# IBVG-DRIVER.net
KiCad netlist of a schematic drawn in Altium Designer
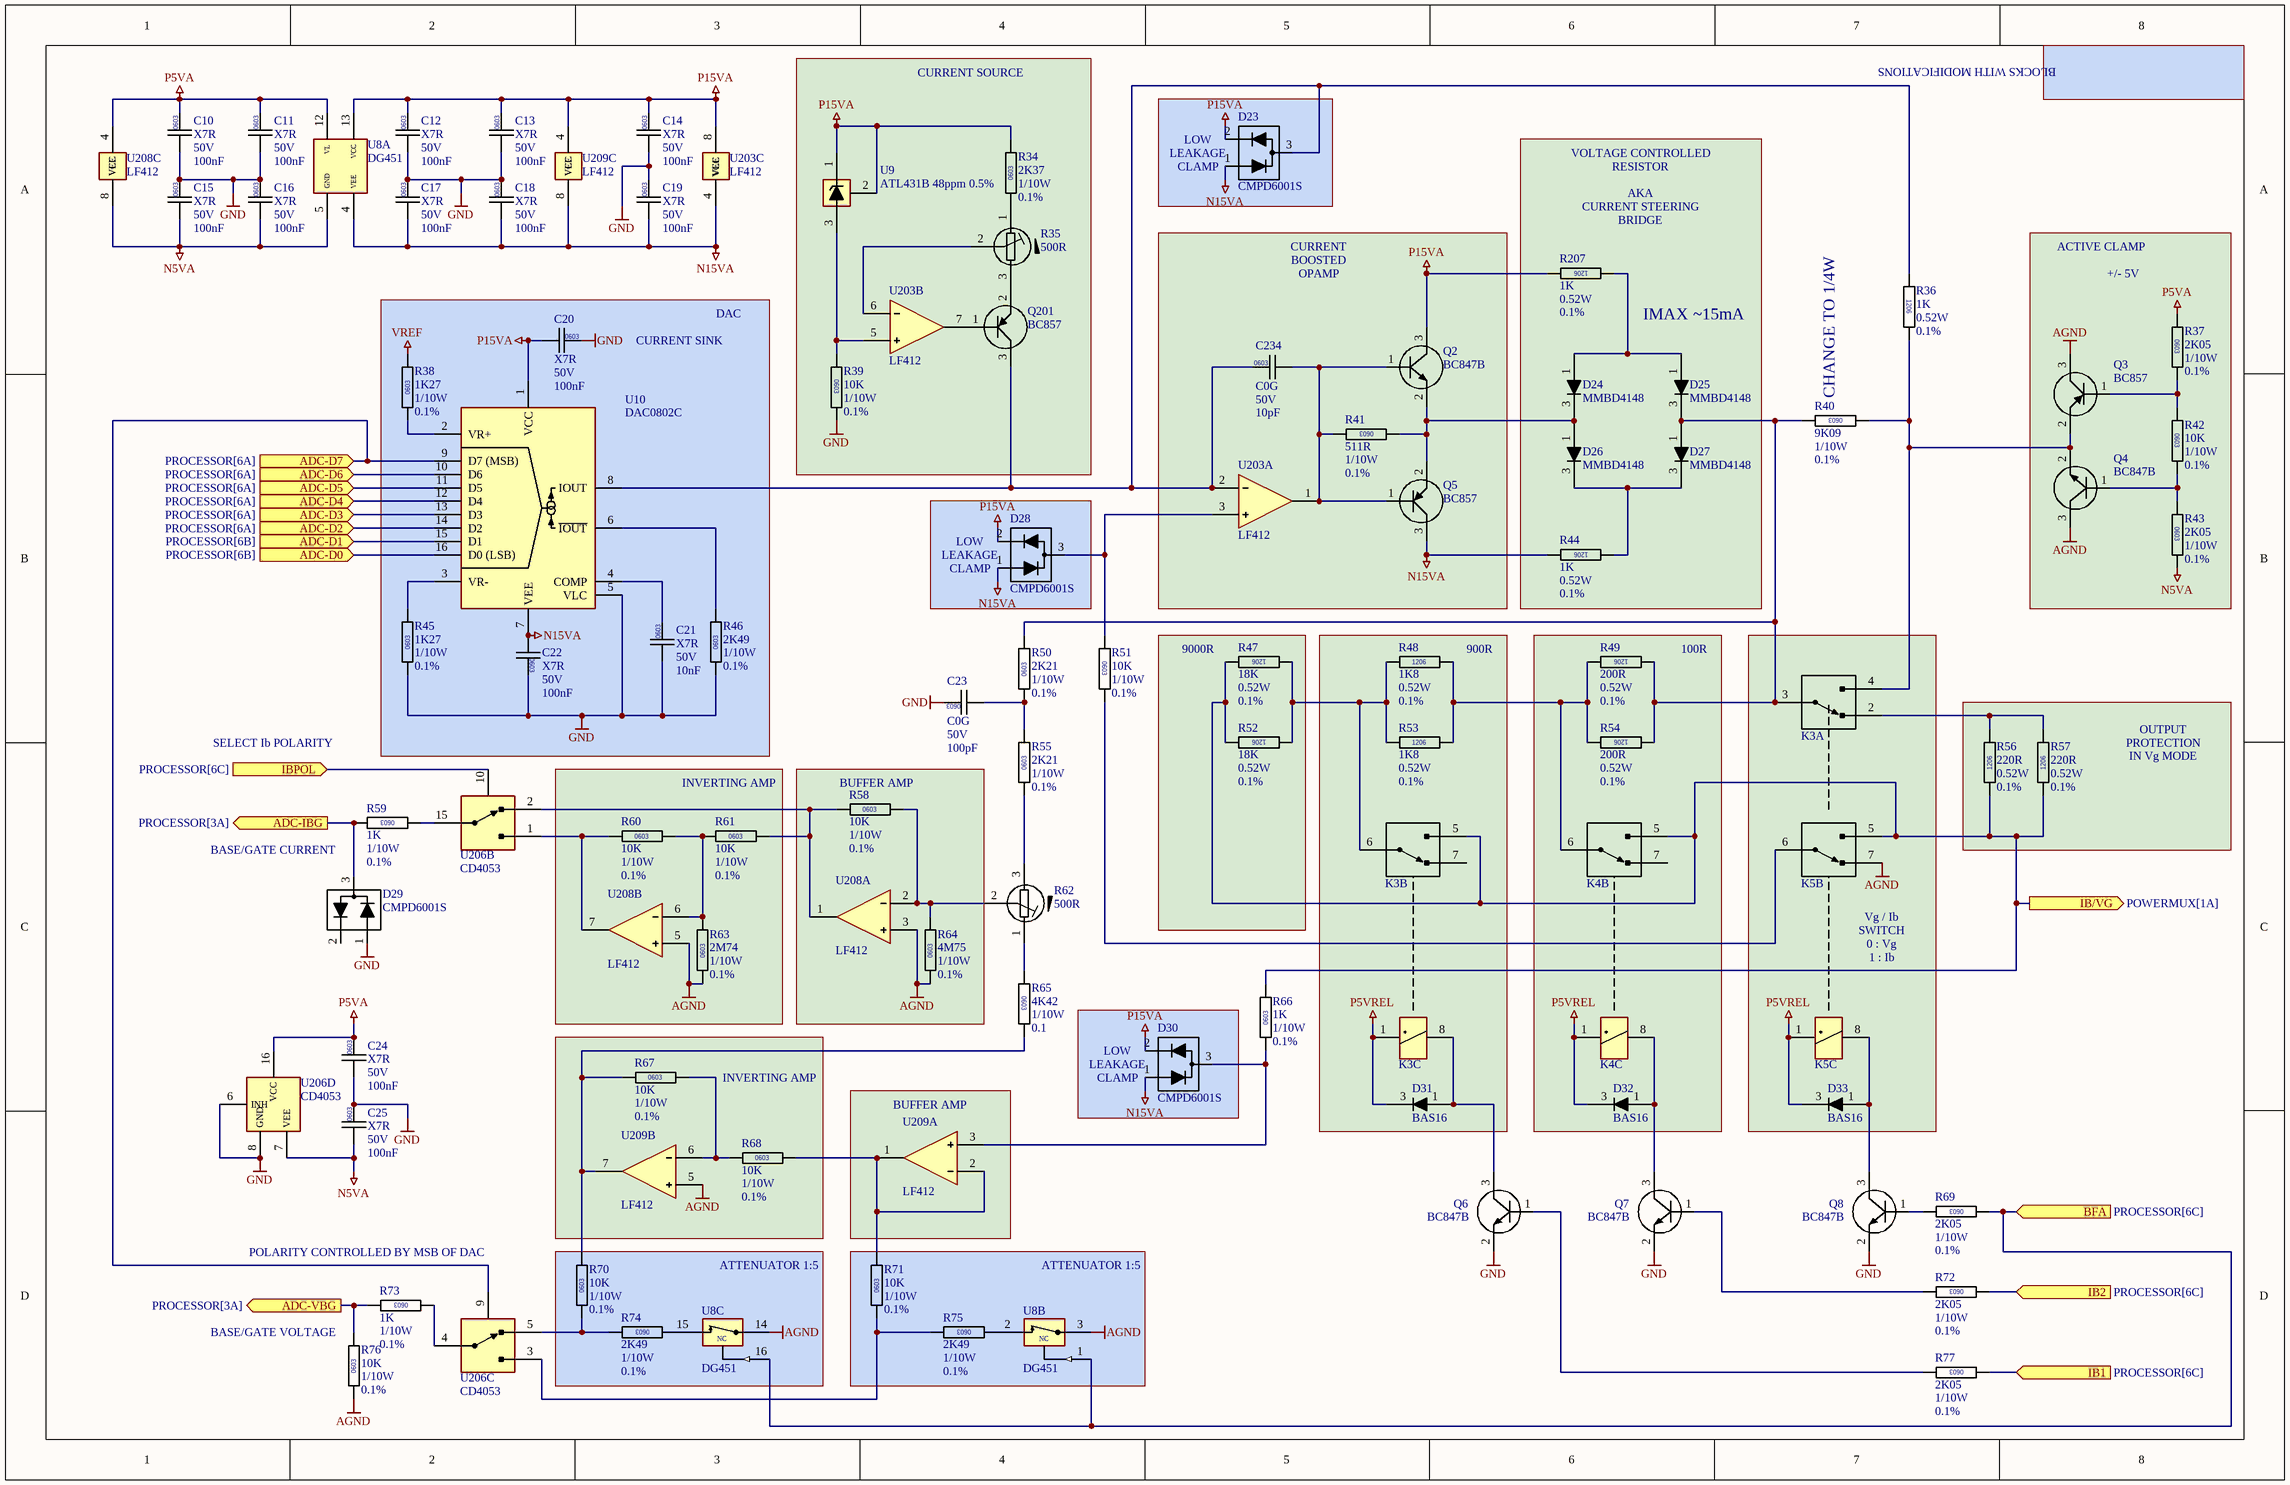
[diagram p0: IBVG-DRIVER.SchDoc]

(export (version "E")
  (design (tool "Eeschema 10.0.6"))
  (components
    (comp (ref "C10")
      (value "CAP0603")
      (footprint "CAPC0603")
      (description "CAPACITOR,CERAMIC,100nF,50V,X7R,0603")
      (fields
        (field (name "DIELECTRIC") "X7R")
        (field (name "VOLTAGE") "50V")
        (field (name "CAPACITANCE") "100nF")
      )
      (libsource (lib "CAPACITORS") (part "CAPC-0603-100nF-50V-X7R"))
    )
    (comp (ref "C11")
      (value "CAP0603")
      (footprint "CAPC0603")
      (description "CAPACITOR,CERAMIC,100nF,50V,X7R,0603")
      (fields
        (field (name "DIELECTRIC") "X7R")
        (field (name "VOLTAGE") "50V")
        (field (name "CAPACITANCE") "100nF")
      )
      (libsource (lib "CAPACITORS") (part "CAPC-0603-100nF-50V-X7R"))
    )
    (comp (ref "C12")
      (value "CAP0603")
      (footprint "CAPC0603")
      (description "CAPACITOR,CERAMIC,100nF,50V,X7R,0603")
      (fields
        (field (name "DIELECTRIC") "X7R")
        (field (name "VOLTAGE") "50V")
        (field (name "CAPACITANCE") "100nF")
      )
      (libsource (lib "CAPACITORS") (part "CAPC-0603-100nF-50V-X7R"))
    )
    (comp (ref "C13")
      (value "CAP0603")
      (footprint "CAPC0603")
      (description "CAPACITOR,CERAMIC,100nF,50V,X7R,0603")
      (fields
        (field (name "DIELECTRIC") "X7R")
        (field (name "VOLTAGE") "50V")
        (field (name "CAPACITANCE") "100nF")
      )
      (libsource (lib "CAPACITORS") (part "CAPC-0603-100nF-50V-X7R"))
    )
    (comp (ref "C14")
      (value "CAP0603")
      (footprint "CAPC0603")
      (description "CAPACITOR,CERAMIC,100nF,50V,X7R,0603")
      (fields
        (field (name "DIELECTRIC") "X7R")
        (field (name "VOLTAGE") "50V")
        (field (name "CAPACITANCE") "100nF")
      )
      (libsource (lib "CAPACITORS") (part "CAPC-0603-100nF-50V-X7R"))
    )
    (comp (ref "C15")
      (value "CAP0603")
      (footprint "CAPC0603")
      (description "CAPACITOR,CERAMIC,100nF,50V,X7R,0603")
      (fields
        (field (name "DIELECTRIC") "X7R")
        (field (name "VOLTAGE") "50V")
        (field (name "CAPACITANCE") "100nF")
      )
      (libsource (lib "CAPACITORS") (part "CAPC-0603-100nF-50V-X7R"))
    )
    (comp (ref "C16")
      (value "CAP0603")
      (footprint "CAPC0603")
      (description "CAPACITOR,CERAMIC,100nF,50V,X7R,0603")
      (fields
        (field (name "DIELECTRIC") "X7R")
        (field (name "VOLTAGE") "50V")
        (field (name "CAPACITANCE") "100nF")
      )
      (libsource (lib "CAPACITORS") (part "CAPC-0603-100nF-50V-X7R"))
    )
    (comp (ref "C17")
      (value "CAP0603")
      (footprint "CAPC0603")
      (description "CAPACITOR,CERAMIC,100nF,50V,X7R,0603")
      (fields
        (field (name "DIELECTRIC") "X7R")
        (field (name "VOLTAGE") "50V")
        (field (name "CAPACITANCE") "100nF")
      )
      (libsource (lib "CAPACITORS") (part "CAPC-0603-100nF-50V-X7R"))
    )
    (comp (ref "C18")
      (value "CAP0603")
      (footprint "CAPC0603")
      (description "CAPACITOR,CERAMIC,100nF,50V,X7R,0603")
      (fields
        (field (name "DIELECTRIC") "X7R")
        (field (name "VOLTAGE") "50V")
        (field (name "CAPACITANCE") "100nF")
      )
      (libsource (lib "CAPACITORS") (part "CAPC-0603-100nF-50V-X7R"))
    )
    (comp (ref "C19")
      (value "CAP0603")
      (footprint "CAPC0603")
      (description "CAPACITOR,CERAMIC,100nF,50V,X7R,0603")
      (fields
        (field (name "DIELECTRIC") "X7R")
        (field (name "VOLTAGE") "50V")
        (field (name "CAPACITANCE") "100nF")
      )
      (libsource (lib "CAPACITORS") (part "CAPC-0603-100nF-50V-X7R"))
    )
    (comp (ref "C20")
      (value "CAP0603")
      (footprint "CAPC0603")
      (description "CAPACITOR,CERAMIC,100nF,50V,X7R,0603")
      (fields
        (field (name "DIELECTRIC") "X7R")
        (field (name "VOLTAGE") "50V")
        (field (name "CAPACITANCE") "100nF")
      )
      (libsource (lib "CAPACITORS") (part "CAPC-0603-100nF-50V-X7R"))
    )
    (comp (ref "C21")
      (value "CAP0603")
      (footprint "CAPC0603")
      (description "CAPACITOR,CERAMIC,10nF,50V,X7R,0603")
      (fields
        (field (name "DIELECTRIC") "X7R")
        (field (name "VOLTAGE") "50V")
        (field (name "CAPACITANCE") "10nF")
      )
      (libsource (lib "CAPACITORS") (part "CAPC-0603-10nF-50V-X7R"))
    )
    (comp (ref "C22")
      (value "CAP0603")
      (footprint "CAPC0603")
      (description "CAPACITOR,CERAMIC,100nF,50V,X7R,0603")
      (fields
        (field (name "DIELECTRIC") "X7R")
        (field (name "VOLTAGE") "50V")
        (field (name "CAPACITANCE") "100nF")
      )
      (libsource (lib "CAPACITORS") (part "CAPC-0603-100nF-50V-X7R"))
    )
    (comp (ref "C23")
      (value "CAP0603")
      (footprint "CAPC0603")
      (description "CAPACITOR,CERAMIC,100pF,50V,C0G,0603")
      (fields
        (field (name "DIELECTRIC") "C0G")
        (field (name "VOLTAGE") "50V")
        (field (name "CAPACITANCE") "100pF")
      )
      (libsource (lib "CAPACITORS") (part "CAPC-0603-100pF-50V-C0G"))
    )
    (comp (ref "C24")
      (value "CAP0603")
      (footprint "CAPC0603")
      (description "CAPACITOR,CERAMIC,100nF,50V,X7R,0603")
      (fields
        (field (name "DIELECTRIC") "X7R")
        (field (name "VOLTAGE") "50V")
        (field (name "CAPACITANCE") "100nF")
      )
      (libsource (lib "CAPACITORS") (part "CAPC-0603-100nF-50V-X7R"))
    )
    (comp (ref "C25")
      (value "CAP0603")
      (footprint "CAPC0603")
      (description "CAPACITOR,CERAMIC,100nF,50V,X7R,0603")
      (fields
        (field (name "DIELECTRIC") "X7R")
        (field (name "VOLTAGE") "50V")
        (field (name "CAPACITANCE") "100nF")
      )
      (libsource (lib "CAPACITORS") (part "CAPC-0603-100nF-50V-X7R"))
    )
    (comp (ref "C234")
      (value "CAP0603")
      (footprint "CAPC0603")
      (description "CAPACITOR,CERAMIC,10pF,50V,C0G,0603")
      (fields
        (field (name "DIELECTRIC") "C0G")
        (field (name "VOLTAGE") "50V")
        (field (name "CAPACITANCE") "10pF")
      )
      (libsource (lib "CAPACITORS") (part "CAPC-0603-10PF-50V-C0G"))
    )
    (comp (ref "D23")
      (value "CMPD6001S")
      (footprint "SOT23")
      (description "DIODE,75V,250mA,SOT23,500pA ULTRA LOW LEAKAGE")
      (libsource (lib "DIODES") (part "DIODE-CENTRALSEMI-CMPD6001S"))
    )
    (comp (ref "D24")
      (value "MMBD4148")
      (description "DIODE,RECTIFIER,75V,0.3A,MMBD4148,SOT23")
      (libsource (lib "DIODES") (part "DIODE-RECTIFIER-DIODES-MMBD4148-SOT23"))
    )
    (comp (ref "D25")
      (value "MMBD4148")
      (description "DIODE,RECTIFIER,75V,0.3A,MMBD4148,SOT23")
      (libsource (lib "DIODES") (part "DIODE-RECTIFIER-DIODES-MMBD4148-SOT23"))
    )
    (comp (ref "D26")
      (value "MMBD4148")
      (description "DIODE,RECTIFIER,75V,0.3A,MMBD4148,SOT23")
      (libsource (lib "DIODES") (part "DIODE-RECTIFIER-DIODES-MMBD4148-SOT23"))
    )
    (comp (ref "D27")
      (value "MMBD4148")
      (description "DIODE,RECTIFIER,75V,0.3A,MMBD4148,SOT23")
      (libsource (lib "DIODES") (part "DIODE-RECTIFIER-DIODES-MMBD4148-SOT23"))
    )
    (comp (ref "D28")
      (value "CMPD6001S")
      (footprint "SOT23")
      (description "DIODE,75V,250mA,SOT23,500pA ULTRA LOW LEAKAGE")
      (libsource (lib "DIODES") (part "DIODE-CENTRALSEMI-CMPD6001S"))
    )
    (comp (ref "D29")
      (value "CMPD6001S")
      (footprint "SOT23")
      (description "DIODE,75V,250mA,SOT23,500pA ULTRA LOW LEAKAGE")
      (libsource (lib "DIODES") (part "DIODE-CENTRALSEMI-CMPD6001S"))
    )
    (comp (ref "D30")
      (value "CMPD6001S")
      (footprint "SOT23")
      (description "DIODE,75V,250mA,SOT23,500pA ULTRA LOW LEAKAGE")
      (libsource (lib "DIODES") (part "DIODE-CENTRALSEMI-CMPD6001S"))
    )
    (comp (ref "D31")
      (value "BAS16")
      (footprint "SOT23")
      (description "DIODE,RECTIFIER,75V,0.3A,BAS16,SOT23")
      (libsource (lib "DIODES") (part "DIODE-RECTIFIER-DIODES-BAS16-SOT23"))
    )
    (comp (ref "D32")
      (value "BAS16")
      (footprint "SOT23")
      (description "DIODE,RECTIFIER,75V,0.3A,BAS16,SOT23")
      (libsource (lib "DIODES") (part "DIODE-RECTIFIER-DIODES-BAS16-SOT23"))
    )
    (comp (ref "D33")
      (value "BAS16")
      (footprint "SOT23")
      (description "DIODE,RECTIFIER,75V,0.3A,BAS16,SOT23")
      (libsource (lib "DIODES") (part "DIODE-RECTIFIER-DIODES-BAS16-SOT23"))
    )
    (comp (ref "K3")
      (value "RELAY-KEMET-UA2-5NJ")
      (footprint "RELAY-KEMET-UA2-5NJ")
      (description "RELAY,DPDT,1A,250VAC,220VDC,5V COIL,KEMET,UA2-5NJ")
      (libsource (lib "RELAYS") (part "RELAY-KEMET-UA2-5NJ"))
    )
    (comp (ref "K4")
      (value "RELAY-KEMET-UA2-5NJ")
      (footprint "RELAY-KEMET-UA2-5NJ")
      (description "RELAY,DPDT,1A,250VAC,220VDC,5V COIL,KEMET,UA2-5NJ")
      (libsource (lib "RELAYS") (part "RELAY-KEMET-UA2-5NJ"))
    )
    (comp (ref "K5")
      (value "RELAY-KEMET-UA2-5NJ")
      (footprint "RELAY-KEMET-UA2-5NJ")
      (description "RELAY,DPDT,1A,250VAC,220VDC,5V COIL,KEMET,UA2-5NJ")
      (libsource (lib "") (part "RELAY-KEMET-UA2-5NJ_1"))
    )
    (comp (ref "Q2")
      (value "BC847B")
      (footprint "SOT23")
      (description "XSTR,NPN,45V,0.1A,,BC847B,SOT23")
      (libsource (lib "TRANSISTORS") (part "XSTR-NPN-BC847"))
    )
    (comp (ref "Q3")
      (value "BC857")
      (footprint "SOT23")
      (description "XSTR,PNP,SOT23,BC857,SOT23")
      (libsource (lib "TRANSISTORS") (part "XSTR-PNP-BC857"))
    )
    (comp (ref "Q4")
      (value "BC847B")
      (footprint "SOT23")
      (description "XSTR,NPN,45V,0.1A,,BC847B,SOT23")
      (libsource (lib "TRANSISTORS") (part "XSTR-NPN-BC847"))
    )
    (comp (ref "Q5")
      (value "BC857")
      (footprint "SOT23")
      (description "XSTR,PNP,SOT23,BC857,SOT23")
      (libsource (lib "TRANSISTORS") (part "XSTR-PNP-BC857"))
    )
    (comp (ref "Q6")
      (value "BC847B")
      (footprint "SOT23")
      (description "XSTR,NPN,45V,0.1A,,BC847B,SOT23")
      (libsource (lib "TRANSISTORS") (part "XSTR-NPN-BC847"))
    )
    (comp (ref "Q7")
      (value "BC847B")
      (footprint "SOT23")
      (description "XSTR,NPN,45V,0.1A,,BC847B,SOT23")
      (libsource (lib "TRANSISTORS") (part "XSTR-NPN-BC847"))
    )
    (comp (ref "Q8")
      (value "BC847B")
      (footprint "SOT23")
      (description "XSTR,NPN,45V,0.1A,,BC847B,SOT23")
      (libsource (lib "TRANSISTORS") (part "XSTR-NPN-BC847"))
    )
    (comp (ref "Q201")
      (value "BC857")
      (footprint "SOT23")
      (description "XSTR,PNP,SOT23,BC857,SOT23")
      (libsource (lib "TRANSISTORS") (part "XSTR-PNP-BC857"))
    )
    (comp (ref "R34")
      (value "2K37")
      (footprint "RESC0603")
      (description "RESISTOR,2K37,0.1%,100mW,0603 (1608)")
      (fields
        (field (name "POWER") "1/10W")
        (field (name "TOLERANCE") "0.1%")
        (field (name "Comment") "RESC0603")
      )
      (libsource (lib "RESISTORS") (part "RESC-0603-2K37-0.1%-1/10W"))
    )
    (comp (ref "R35")
      (value "500R")
      (footprint "TRIMMER-BOURNS-3214X")
      (description "RESISTOR,MULTITURN,VERTICAL,5T,500R")
      (fields (field (name "Comment") "TRIMMER-BOURNS-3214X-1-501"))
      (libsource (lib "RESISTORS") (part "TRIMMER-BOURNS-3214X-1-501"))
    )
    (comp (ref "R36")
      (value "1K")
      (footprint "RESC1206")
      (description "RESISTOR,1K,1206,0.1%,520mW,1206")
      (fields
        (field (name "POWER") "0.52W")
        (field (name "TOLERANCE") "0.1%")
        (field (name "Comment") "RESC1206")
      )
      (libsource (lib "RESISTORS") (part "RESC-1206-1K-0.1%-1/2W"))
    )
    (comp (ref "R37")
      (value "2K05")
      (footprint "RESC0603")
      (description "RESISTOR,2K05,0.11%,100mW,0603 (1608)")
      (fields
        (field (name "POWER") "1/10W")
        (field (name "TOLERANCE") "0.1%")
        (field (name "Comment") "RESC0603")
      )
      (libsource (lib "RESISTORS") (part "RESC-0603-2K05-0.1%-1/10W"))
    )
    (comp (ref "R38")
      (value "1K27")
      (footprint "RESC0603")
      (description "RESISTOR,1K27,0.1%,100mW,0603 (1608)")
      (fields
        (field (name "POWER") "1/10W")
        (field (name "TOLERANCE") "0.1%")
        (field (name "Comment") "RESC0603")
      )
      (libsource (lib "RESISTORS") (part "RESC-0603-1K27-0.1%-1/10W"))
    )
    (comp (ref "R39")
      (value "10K")
      (footprint "RESC0603")
      (description "RESISTOR,10K,0.1%,100mW,0603 (1608)")
      (fields
        (field (name "POWER") "1/10W")
        (field (name "TOLERANCE") "0.1%")
        (field (name "Comment") "RESC0603")
      )
      (libsource (lib "RESISTORS") (part "RESC-0603-10K-0.1%-1/10W"))
    )
    (comp (ref "R40")
      (value "9K09")
      (footprint "RESC0603")
      (description "RESISTOR,9K09,0.1%,100mW,0603 (1608)")
      (fields
        (field (name "POWER") "1/10W")
        (field (name "TOLERANCE") "0.1%")
        (field (name "Comment") "RESC0603")
      )
      (libsource (lib "RESISTORS") (part "RESC-0603-9K09-0.1%-1/10W"))
    )
    (comp (ref "R41")
      (value "511R")
      (footprint "RESC0603")
      (description "RESISTOR,511R,0.1%,100mW,0603 (1608)")
      (fields
        (field (name "POWER") "1/10W")
        (field (name "TOLERANCE") "0.1%")
        (field (name "Comment") "RESC0603")
      )
      (libsource (lib "RESISTORS") (part "RESC-0603-511R-0.1%-1/10W"))
    )
    (comp (ref "R42")
      (value "10K")
      (footprint "RESC0603")
      (description "RESISTOR,10K,0.1%,100mW,0603 (1608)")
      (fields
        (field (name "POWER") "1/10W")
        (field (name "TOLERANCE") "0.1%")
        (field (name "Comment") "RESC0603")
      )
      (libsource (lib "RESISTORS") (part "RESC-0603-10K-0.1%-1/10W"))
    )
    (comp (ref "R43")
      (value "2K05")
      (footprint "RESC0603")
      (description "RESISTOR,2K05,0.11%,100mW,0603 (1608)")
      (fields
        (field (name "POWER") "1/10W")
        (field (name "TOLERANCE") "0.1%")
        (field (name "Comment") "RESC0603")
      )
      (libsource (lib "RESISTORS") (part "RESC-0603-2K05-0.1%-1/10W"))
    )
    (comp (ref "R44")
      (value "1K")
      (footprint "RESC1206")
      (description "RESISTOR,1K,1206,0.1%,520mW,1206")
      (fields
        (field (name "POWER") "0.52W")
        (field (name "TOLERANCE") "0.1%")
        (field (name "Comment") "RESC1206")
      )
      (libsource (lib "RESISTORS") (part "RESC-1206-1K-0.1%-1/2W"))
    )
    (comp (ref "R45")
      (value "1K27")
      (footprint "RESC0603")
      (description "RESISTOR,1K27,0.1%,100mW,0603 (1608)")
      (fields
        (field (name "POWER") "1/10W")
        (field (name "TOLERANCE") "0.1%")
        (field (name "Comment") "RESC0603")
      )
      (libsource (lib "RESISTORS") (part "RESC-0603-1K27-0.1%-1/10W"))
    )
    (comp (ref "R46")
      (value "2K49")
      (footprint "RESC0603")
      (description "RESISTOR,2K49,0.1%,100mW,0603 (1608)")
      (fields
        (field (name "POWER") "1/10W")
        (field (name "TOLERANCE") "0.1%")
        (field (name "Comment") "RESC0603")
      )
      (libsource (lib "RESISTORS") (part "RESC-0603-2K49-0.1%-1/10W"))
    )
    (comp (ref "R47")
      (value "18K")
      (footprint "RESC1206")
      (description "RESISTOR,18K,1206,0.1%,520mW,1206")
      (fields
        (field (name "POWER") "0.52W")
        (field (name "TOLERANCE") "0.1%")
        (field (name "Comment") "RESC1206")
      )
      (libsource (lib "RESISTORS") (part "RESC-1206-18K-0.1%-1/2W"))
    )
    (comp (ref "R48")
      (value "1K8")
      (footprint "RESC1206")
      (description "RESISTOR,1K8,1206,0.1%,520mW,1206")
      (fields
        (field (name "POWER") "0.52W")
        (field (name "TOLERANCE") "0.1%")
        (field (name "Comment") "RESC1206")
      )
      (libsource (lib "RESISTORS") (part "RESC-1206-1K8-0.1%-1/2W"))
    )
    (comp (ref "R49")
      (value "200R")
      (footprint "RESC1206")
      (description "RESISTOR,200R,1206,0.1%,520mW,1206")
      (fields
        (field (name "POWER") "0.52W")
        (field (name "TOLERANCE") "0.1%")
        (field (name "Comment") "RESC1206")
      )
      (libsource (lib "RESISTORS") (part "RESC-1206-200R-0.1%-1/2W"))
    )
    (comp (ref "R50")
      (value "2K21")
      (footprint "RESC0603")
      (description "RESISTOR,2K21,0.1%,100mW,0603 (1608)")
      (fields
        (field (name "POWER") "1/10W")
        (field (name "TOLERANCE") "0.1%")
        (field (name "Comment") "RESC0603")
      )
      (libsource (lib "RESISTORS") (part "RESC-0603-2K21-0.1%-1/10W"))
    )
    (comp (ref "R51")
      (value "10K")
      (footprint "RESC0603")
      (description "RESISTOR,10K,0.1%,100mW,0603 (1608)")
      (fields
        (field (name "POWER") "1/10W")
        (field (name "TOLERANCE") "0.1%")
        (field (name "Comment") "RESC0603")
      )
      (libsource (lib "RESISTORS") (part "RESC-0603-10K-0.1%-1/10W"))
    )
    (comp (ref "R52")
      (value "18K")
      (footprint "RESC1206")
      (description "RESISTOR,18K,1206,0.1%,520mW,1206")
      (fields
        (field (name "POWER") "0.52W")
        (field (name "TOLERANCE") "0.1%")
        (field (name "Comment") "RESC1206")
      )
      (libsource (lib "RESISTORS") (part "RESC-1206-18K-0.1%-1/2W"))
    )
    (comp (ref "R53")
      (value "1K8")
      (footprint "RESC1206")
      (description "RESISTOR,1K8,1206,0.1%,520mW,1206")
      (fields
        (field (name "POWER") "0.52W")
        (field (name "TOLERANCE") "0.1%")
        (field (name "Comment") "RESC1206")
      )
      (libsource (lib "RESISTORS") (part "RESC-1206-1K8-0.1%-1/2W"))
    )
    (comp (ref "R54")
      (value "200R")
      (footprint "RESC1206")
      (description "RESISTOR,200R,1206,0.1%,520mW,1206")
      (fields
        (field (name "POWER") "0.52W")
        (field (name "TOLERANCE") "0.1%")
        (field (name "Comment") "RESC1206")
      )
      (libsource (lib "RESISTORS") (part "RESC-1206-200R-0.1%-1/2W"))
    )
    (comp (ref "R55")
      (value "2K21")
      (footprint "RESC0603")
      (description "RESISTOR,2K21,0.1%,100mW,0603 (1608)")
      (fields
        (field (name "POWER") "1/10W")
        (field (name "TOLERANCE") "0.1%")
        (field (name "Comment") "RESC0603")
      )
      (libsource (lib "RESISTORS") (part "RESC-0603-2K21-0.1%-1/10W"))
    )
    (comp (ref "R56")
      (value "220R")
      (footprint "RESC1206")
      (description "RESISTOR,220R,1206,0.1%,520mW,1206")
      (fields
        (field (name "POWER") "0.52W")
        (field (name "TOLERANCE") "0.1%")
        (field (name "Comment") "RESC1206")
      )
      (libsource (lib "RESISTORS") (part "RESC-1206-220R-0.1%-1/2W"))
    )
    (comp (ref "R57")
      (value "220R")
      (footprint "RESC1206")
      (description "RESISTOR,220R,1206,0.1%,520mW,1206")
      (fields
        (field (name "POWER") "0.52W")
        (field (name "TOLERANCE") "0.1%")
        (field (name "Comment") "RESC1206")
      )
      (libsource (lib "RESISTORS") (part "RESC-1206-220R-0.1%-1/2W"))
    )
    (comp (ref "R58")
      (value "10K")
      (footprint "RESC0603")
      (description "RESISTOR,10K,0.1%,100mW,0603 (1608)")
      (fields
        (field (name "POWER") "1/10W")
        (field (name "TOLERANCE") "0.1%")
        (field (name "Comment") "RESC0603")
      )
      (libsource (lib "RESISTORS") (part "RESC-0603-10K-0.1%-1/10W"))
    )
    (comp (ref "R59")
      (value "1K")
      (footprint "RESC0603")
      (description "RESISTOR,1K,0.1%,100mW,0603 (1608)")
      (fields
        (field (name "POWER") "1/10W")
        (field (name "TOLERANCE") "0.1%")
        (field (name "Comment") "RESC0603")
      )
      (libsource (lib "RESISTORS") (part "RESC-0603-1K-0.1%-1/10W"))
    )
    (comp (ref "R60")
      (value "10K")
      (footprint "RESC0603")
      (description "RESISTOR,10K,0.1%,100mW,0603 (1608)")
      (fields
        (field (name "POWER") "1/10W")
        (field (name "TOLERANCE") "0.1%")
        (field (name "Comment") "RESC0603")
      )
      (libsource (lib "RESISTORS") (part "RESC-0603-10K-0.1%-1/10W"))
    )
    (comp (ref "R61")
      (value "10K")
      (footprint "RESC0603")
      (description "RESISTOR,10K,0.1%,100mW,0603 (1608)")
      (fields
        (field (name "POWER") "1/10W")
        (field (name "TOLERANCE") "0.1%")
        (field (name "Comment") "RESC0603")
      )
      (libsource (lib "RESISTORS") (part "RESC-0603-10K-0.1%-1/10W"))
    )
    (comp (ref "R62")
      (value "500R")
      (footprint "TRIMMER-BOURNS-3214X")
      (description "RESISTOR,MULTITURN,VERTICAL,5T,500R")
      (fields (field (name "Comment") "TRIMMER-BOURNS-3214X-1-501"))
      (libsource (lib "RESISTORS") (part "TRIMMER-BOURNS-3214X-1-501"))
    )
    (comp (ref "R63")
      (value "2M74")
      (footprint "RESC0603")
      (description "RESISTOR,2M74,0.1%,100mW,0603 (1608)")
      (fields
        (field (name "POWER") "1/10W")
        (field (name "TOLERANCE") "0.1%")
        (field (name "Comment") "RESC0603")
      )
      (libsource (lib "RESISTORS") (part "RESC-0603-2M74-0.1%-1/10W"))
    )
    (comp (ref "R64")
      (value "4M75")
      (footprint "RESC0603")
      (description "RESISTOR,4M75,0.1%,100mW,0603 (1608)")
      (fields
        (field (name "POWER") "1/10W")
        (field (name "TOLERANCE") "0.1%")
        (field (name "Comment") "RESC0603")
      )
      (libsource (lib "RESISTORS") (part "RESC-0603-4M75-1%-1/10W"))
    )
    (comp (ref "R65")
      (value "4K42")
      (footprint "RESC0603")
      (description "RESISTOR,4K42,0.1%,100mW,0603 (1608)")
      (fields
        (field (name "POWER") "1/10W")
        (field (name "TOLERANCE") "0.1")
        (field (name "Comment") "RESC0603")
      )
      (libsource (lib "RESISTORS") (part "RESC-0603-4K42-0.1%-1/10W"))
    )
    (comp (ref "R66")
      (value "1K")
      (footprint "RESC0603")
      (description "RESISTOR,1K,0.1%,100mW,0603 (1608)")
      (fields
        (field (name "POWER") "1/10W")
        (field (name "TOLERANCE") "0.1%")
        (field (name "Comment") "RESC0603")
      )
      (libsource (lib "RESISTORS") (part "RESC-0603-1K-0.1%-1/10W"))
    )
    (comp (ref "R67")
      (value "10K")
      (footprint "RESC0603")
      (description "RESISTOR,10K,0.1%,100mW,0603 (1608)")
      (fields
        (field (name "POWER") "1/10W")
        (field (name "TOLERANCE") "0.1%")
        (field (name "Comment") "RESC0603")
      )
      (libsource (lib "RESISTORS") (part "RESC-0603-10K-0.1%-1/10W"))
    )
    (comp (ref "R68")
      (value "10K")
      (footprint "RESC0603")
      (description "RESISTOR,10K,0.1%,100mW,0603 (1608)")
      (fields
        (field (name "POWER") "1/10W")
        (field (name "TOLERANCE") "0.1%")
        (field (name "Comment") "RESC0603")
      )
      (libsource (lib "RESISTORS") (part "RESC-0603-10K-0.1%-1/10W"))
    )
    (comp (ref "R69")
      (value "2K05")
      (footprint "RESC0603")
      (description "RESISTOR,2K05,0.11%,100mW,0603 (1608)")
      (fields
        (field (name "POWER") "1/10W")
        (field (name "TOLERANCE") "0.1%")
        (field (name "Comment") "RESC0603")
      )
      (libsource (lib "RESISTORS") (part "RESC-0603-2K05-0.1%-1/10W"))
    )
    (comp (ref "R70")
      (value "10K")
      (footprint "RESC0603")
      (description "RESISTOR,10K,0.1%,100mW,0603 (1608)")
      (fields
        (field (name "POWER") "1/10W")
        (field (name "TOLERANCE") "0.1%")
        (field (name "Comment") "RESC0603")
      )
      (libsource (lib "RESISTORS") (part "RESC-0603-10K-0.1%-1/10W"))
    )
    (comp (ref "R71")
      (value "10K")
      (footprint "RESC0603")
      (description "RESISTOR,10K,0.1%,100mW,0603 (1608)")
      (fields
        (field (name "POWER") "1/10W")
        (field (name "TOLERANCE") "0.1%")
        (field (name "Comment") "RESC0603")
      )
      (libsource (lib "RESISTORS") (part "RESC-0603-10K-0.1%-1/10W"))
    )
    (comp (ref "R72")
      (value "2K05")
      (footprint "RESC0603")
      (description "RESISTOR,2K05,0.11%,100mW,0603 (1608)")
      (fields
        (field (name "POWER") "1/10W")
        (field (name "TOLERANCE") "0.1%")
        (field (name "Comment") "RESC0603")
      )
      (libsource (lib "RESISTORS") (part "RESC-0603-2K05-0.1%-1/10W"))
    )
    (comp (ref "R73")
      (value "1K")
      (footprint "RESC0603")
      (description "RESISTOR,1K,0.1%,100mW,0603 (1608)")
      (fields
        (field (name "POWER") "1/10W")
        (field (name "TOLERANCE") "0.1%")
        (field (name "Comment") "RESC0603")
      )
      (libsource (lib "RESISTORS") (part "RESC-0603-1K-0.1%-1/10W"))
    )
    (comp (ref "R74")
      (value "2K49")
      (footprint "RESC0603")
      (description "RESISTOR,2K49,0.1%,100mW,0603 (1608)")
      (fields
        (field (name "POWER") "1/10W")
        (field (name "TOLERANCE") "0.1%")
        (field (name "Comment") "RESC0603")
      )
      (libsource (lib "RESISTORS") (part "RESC-0603-2K49-0.1%-1/10W"))
    )
    (comp (ref "R75")
      (value "2K49")
      (footprint "RESC0603")
      (description "RESISTOR,2K49,0.1%,100mW,0603 (1608)")
      (fields
        (field (name "POWER") "1/10W")
        (field (name "TOLERANCE") "0.1%")
        (field (name "Comment") "RESC0603")
      )
      (libsource (lib "RESISTORS") (part "RESC-0603-2K49-0.1%-1/10W"))
    )
    (comp (ref "R76")
      (value "10K")
      (footprint "RESC0603")
      (description "RESISTOR,10K,0.1%,100mW,0603 (1608)")
      (fields
        (field (name "POWER") "1/10W")
        (field (name "TOLERANCE") "0.1%")
        (field (name "Comment") "RESC0603")
      )
      (libsource (lib "RESISTORS") (part "RESC-0603-10K-0.1%-1/10W"))
    )
    (comp (ref "R77")
      (value "2K05")
      (footprint "RESC0603")
      (description "RESISTOR,2K05,0.11%,100mW,0603 (1608)")
      (fields
        (field (name "POWER") "1/10W")
        (field (name "TOLERANCE") "0.1%")
        (field (name "Comment") "RESC0603")
      )
      (libsource (lib "RESISTORS") (part "RESC-0603-2K05-0.1%-1/10W"))
    )
    (comp (ref "R207")
      (value "1K")
      (footprint "RESC1206")
      (description "RESISTOR,1K,1206,0.1%,520mW,1206")
      (fields
        (field (name "POWER") "0.52W")
        (field (name "TOLERANCE") "0.1%")
        (field (name "Comment") "RESC1206")
      )
      (libsource (lib "RESISTORS") (part "RESC-1206-1K-0.1%-1/2W"))
    )
    (comp (ref "U8")
      (value "DG451")
      (footprint "SO127P600-16N")
      (description "IC,ANALOG,4XSPST ANALOG SWITCH,NC,,SILICONIX,DG451,SO16")
      (libsource (lib "IC-ANALOG") (part "IC-SILICONIX-DG451"))
    )
    (comp (ref "U9")
      (value "ATL431B 48ppm 0.5%")
      (footprint "SOT23")
      (description "IC,REGULATOR,REFERENCE,SHUNT,0.5%,48ppm,TL431,SOT23")
      (libsource (lib "IC-ANALOG") (part "IC-TI-ATL431B-SOT23"))
    )
    (comp (ref "U10")
      (value "DAC0802C")
      (description "IC,DAC,8 BIT,CURRENT DIFF,TI,DAC0802LCMX/NOPB,SO16")
      (libsource (lib "IC-ADDA") (part "IC-TI-DAC0802LCMX/NOPB"))
    )
    (comp (ref "U203")
      (value "LF412")
      (footprint "SO127P600-8N")
      (description "IC,OPAMP JFET,DUAL,LF412,SO8")
      (libsource (lib "") (part "IC-TI-LF412-S08_2"))
    )
    (comp (ref "U206")
      (value "CD4053")
      (footprint "SO127P600-16N")
      (description "IC,LOGIC,CMOS,4XXX,TRIPLE 2:1 MUX,SPLIT BLOCKS")
      (libsource (lib "IC-4XXX") (part "IC-TI-CD4053-SPLIT"))
    )
    (comp (ref "U208")
      (value "LF412")
      (footprint "SO127P600-8N")
      (description "IC,OPAMP JFET,DUAL,LF412,SO8")
      (libsource (lib "") (part "IC-TI-LF412-S08_1"))
    )
    (comp (ref "U209")
      (value "LF412")
      (footprint "SO127P600-8N")
      (description "IC,OPAMP JFET,DUAL,LF412,SO8")
      (libsource (lib "") (part "IC-TI-LF412-S08_1"))
    )
  )
  (nets
    (net (code "1") (name "/ADC-D0") (class "Default")
      (node (ref "U10") (pin "16") (pinfunction "D0_(LSB)_16") (pintype "passive"))
    )
    (net (code "2") (name "/ADC-D1") (class "Default")
      (node (ref "U10") (pin "15") (pinfunction "D1_15") (pintype "passive"))
    )
    (net (code "3") (name "/ADC-D2") (class "Default")
      (node (ref "U10") (pin "14") (pinfunction "D2_14") (pintype "passive"))
    )
    (net (code "4") (name "/ADC-D3") (class "Default")
      (node (ref "U10") (pin "13") (pinfunction "D3_13") (pintype "passive"))
    )
    (net (code "5") (name "/ADC-D4") (class "Default")
      (node (ref "U10") (pin "12") (pinfunction "D4_12") (pintype "passive"))
    )
    (net (code "6") (name "/ADC-D5") (class "Default")
      (node (ref "U10") (pin "11") (pinfunction "D5_11") (pintype "passive"))
    )
    (net (code "7") (name "/ADC-D6") (class "Default")
      (node (ref "U10") (pin "10") (pinfunction "D6_10") (pintype "passive"))
    )
    (net (code "8") (name "/ADC-D7") (class "Default")
      (node (ref "U10") (pin "9") (pinfunction "D7_(MSB)_9") (pintype "passive"))
      (node (ref "U206") (pin "9") (pinfunction "B_9") (pintype "passive"))
    )
    (net (code "9") (name "/ADC-IBG") (class "Default")
      (node (ref "D29") (pin "3") (pinfunction "A_3") (pintype "passive"))
      (node (ref "R59") (pin "1") (pintype "passive"))
    )
    (net (code "10") (name "/ADC-VBG") (class "Default")
      (node (ref "R73") (pin "1") (pintype "passive"))
      (node (ref "R76") (pin "1") (pintype "passive"))
    )
    (net (code "11") (name "/BFA") (class "Default")
      (node (ref "R69") (pin "1") (pintype "passive"))
      (node (ref "U8") (pin "1") (pinfunction "1_1") (pintype "input"))
      (node (ref "U8") (pin "16") (pinfunction "16_16") (pintype "input"))
    )
    (net (code "12") (name "/IB1") (class "Default") (node (ref "R77") (pin "1") (pintype "passive")))
    (net (code "13") (name "/IB2") (class "Default") (node (ref "R72") (pin "1") (pintype "passive")))
    (net (code "14") (name "/IBPOL") (class "Default")
      (node (ref "U206") (pin "10") (pinfunction "A_10") (pintype "passive"))
    )
    (net (code "15") (name "/IB{slash}VG") (class "Default")
      (node (ref "K3") (pin "5") (pinfunction "NO_5") (pintype "passive"))
      (node (ref "K4") (pin "5") (pinfunction "NO_5") (pintype "passive"))
      (node (ref "K5") (pin "5") (pinfunction "NO_5") (pintype "passive"))
      (node (ref "R47") (pin "2") (pintype "passive"))
      (node (ref "R52") (pin "2") (pintype "passive"))
      (node (ref "R56") (pin "2") (pintype "passive"))
      (node (ref "R57") (pin "2") (pintype "passive"))
      (node (ref "R66") (pin "1") (pintype "passive"))
    )
    (net (code "16") (name "AGND") (class "Default")
      (node (ref "K5") (pin "7") (pinfunction "NC_7") (pintype "passive"))
      (node (ref "Q3") (pin "3") (pinfunction "C_3") (pintype "passive"))
      (node (ref "Q4") (pin "3") (pinfunction "C_3") (pintype "passive"))
      (node (ref "R63") (pin "2") (pintype "passive"))
      (node (ref "R64") (pin "2") (pintype "passive"))
      (node (ref "R76") (pin "2") (pintype "passive"))
      (node (ref "U208") (pin "3") (pinfunction "+_3") (pintype "passive"))
      (node (ref "U208") (pin "5") (pinfunction "+_5") (pintype "passive"))
      (node (ref "U209") (pin "5") (pinfunction "+_5") (pintype "passive"))
      (node (ref "U8") (pin "14") (pinfunction "14_14") (pintype "passive"))
      (node (ref "U8") (pin "3") (pinfunction "3_3") (pintype "passive"))
    )
    (net (code "17") (name "GND") (class "Default")
      (node (ref "C10") (pin "2") (pintype "passive"))
      (node (ref "C11") (pin "2") (pintype "passive"))
      (node (ref "C12") (pin "2") (pintype "passive"))
      (node (ref "C13") (pin "2") (pintype "passive"))
      (node (ref "C14") (pin "2") (pintype "passive"))
      (node (ref "C15") (pin "1") (pintype "passive"))
      (node (ref "C16") (pin "1") (pintype "passive"))
      (node (ref "C17") (pin "1") (pintype "passive"))
      (node (ref "C18") (pin "1") (pintype "passive"))
      (node (ref "C19") (pin "1") (pintype "passive"))
      (node (ref "C20") (pin "1") (pintype "passive"))
      (node (ref "C21") (pin "2") (pintype "passive"))
      (node (ref "C22") (pin "1") (pintype "passive"))
      (node (ref "C23") (pin "1") (pintype "passive"))
      (node (ref "C24") (pin "2") (pintype "passive"))
      (node (ref "C25") (pin "1") (pintype "passive"))
      (node (ref "D29") (pin "1") (pinfunction "K_1") (pintype "passive"))
      (node (ref "Q6") (pin "2") (pinfunction "E_2") (pintype "passive"))
      (node (ref "Q7") (pin "2") (pinfunction "E_2") (pintype "passive"))
      (node (ref "Q8") (pin "2") (pinfunction "E_2") (pintype "passive"))
      (node (ref "R39") (pin "1") (pintype "passive"))
      (node (ref "R45") (pin "2") (pintype "passive"))
      (node (ref "R46") (pin "2") (pintype "passive"))
      (node (ref "U10") (pin "5") (pinfunction "VLC_5") (pintype "passive"))
      (node (ref "U206") (pin "6") (pinfunction "INH_6") (pintype "passive"))
      (node (ref "U206") (pin "8") (pinfunction "GND_8") (pintype "passive"))
    )
    (net (code "18") (name "N5VA") (class "Default")
      (node (ref "C15") (pin "2") (pintype "passive"))
      (node (ref "C16") (pin "2") (pintype "passive"))
      (node (ref "C25") (pin "2") (pintype "passive"))
      (node (ref "R43") (pin "2") (pintype "passive"))
      (node (ref "U206") (pin "7") (pinfunction "VEE_7") (pintype "passive"))
      (node (ref "U208") (pin "8") (pinfunction "VCC_8") (pintype "passive"))
      (node (ref "U8") (pin "5") (pinfunction "GND_5") (pintype "power_in"))
    )
    (net (code "19") (name "N15VA") (class "Default")
      (node (ref "C17") (pin "2") (pintype "passive"))
      (node (ref "C18") (pin "2") (pintype "passive"))
      (node (ref "C19") (pin "2") (pintype "passive"))
      (node (ref "C22") (pin "2") (pintype "passive"))
      (node (ref "D23") (pin "1") (pinfunction "K_1") (pintype "passive"))
      (node (ref "D28") (pin "1") (pinfunction "K_1") (pintype "passive"))
      (node (ref "D30") (pin "1") (pinfunction "K_1") (pintype "passive"))
      (node (ref "Q5") (pin "3") (pinfunction "C_3") (pintype "passive"))
      (node (ref "R44") (pin "1") (pintype "passive"))
      (node (ref "U10") (pin "7") (pinfunction "VEE_7") (pintype "passive"))
      (node (ref "U203") (pin "4") (pinfunction "VEE_4") (pintype "passive"))
      (node (ref "U209") (pin "8") (pinfunction "VCC_8") (pintype "passive"))
      (node (ref "U8") (pin "4") (pinfunction "VEE_4") (pintype "power_in"))
    )
    (net (code "20") (name "Net-(C23-Pad2)") (class "Default")
      (node (ref "C23") (pin "2") (pintype "passive"))
      (node (ref "R50") (pin "2") (pintype "passive"))
      (node (ref "R55") (pin "1") (pintype "passive"))
    )
    (net (code "21") (name "Net-(D24-A)") (class "Default")
      (node (ref "D24") (pin "1") (pinfunction "A_1") (pintype "passive"))
      (node (ref "D25") (pin "1") (pinfunction "A_1") (pintype "passive"))
      (node (ref "R207") (pin "2") (pintype "passive"))
    )
    (net (code "22") (name "Net-(D24-K)") (class "Default")
      (node (ref "D24") (pin "3") (pinfunction "K_3") (pintype "passive"))
      (node (ref "D26") (pin "1") (pinfunction "A_1") (pintype "passive"))
      (node (ref "Q2") (pin "2") (pinfunction "E_2") (pintype "passive"))
      (node (ref "Q5") (pin "2") (pinfunction "E_2") (pintype "passive"))
      (node (ref "R41") (pin "2") (pintype "passive"))
    )
    (net (code "23") (name "Net-(D25-K)") (class "Default")
      (node (ref "D25") (pin "3") (pinfunction "K_3") (pintype "passive"))
      (node (ref "D27") (pin "1") (pinfunction "A_1") (pintype "passive"))
      (node (ref "K3") (pin "3") (pinfunction "COM_3") (pintype "passive"))
      (node (ref "R40") (pin "1") (pintype "passive"))
      (node (ref "R49") (pin "1") (pintype "passive"))
      (node (ref "R50") (pin "1") (pintype "passive"))
      (node (ref "R54") (pin "1") (pintype "passive"))
    )
    (net (code "24") (name "Net-(D26-K)") (class "Default")
      (node (ref "D26") (pin "3") (pinfunction "K_3") (pintype "passive"))
      (node (ref "D27") (pin "3") (pinfunction "K_3") (pintype "passive"))
      (node (ref "R44") (pin "2") (pintype "passive"))
    )
    (net (code "25") (name "Net-(D31-A)") (class "Default")
      (node (ref "D31") (pin "1") (pinfunction "A_1") (pintype "passive"))
      (node (ref "K3") (pin "8") (pinfunction "8_8") (pintype "passive"))
      (node (ref "Q6") (pin "3") (pinfunction "C_3") (pintype "passive"))
    )
    (net (code "26") (name "Net-(D32-A)") (class "Default")
      (node (ref "D32") (pin "1") (pinfunction "A_1") (pintype "passive"))
      (node (ref "K4") (pin "8") (pinfunction "8_8") (pintype "passive"))
      (node (ref "Q7") (pin "3") (pinfunction "C_3") (pintype "passive"))
    )
    (net (code "27") (name "Net-(D33-A)") (class "Default")
      (node (ref "D33") (pin "1") (pinfunction "A_1") (pintype "passive"))
      (node (ref "K5") (pin "8") (pinfunction "8_8") (pintype "passive"))
      (node (ref "Q8") (pin "3") (pinfunction "C_3") (pintype "passive"))
    )
    (net (code "28") (name "Net-(K3A-NC)") (class "Default")
      (node (ref "K3") (pin "2") (pinfunction "NC_2") (pintype "passive"))
      (node (ref "R56") (pin "1") (pintype "passive"))
      (node (ref "R57") (pin "1") (pintype "passive"))
    )
    (net (code "29") (name "Net-(K3A-NO)") (class "Default")
      (node (ref "K3") (pin "4") (pinfunction "NO_4") (pintype "passive"))
      (node (ref "Q3") (pin "2") (pinfunction "E_2") (pintype "passive"))
      (node (ref "Q4") (pin "2") (pinfunction "E_2") (pintype "passive"))
      (node (ref "R36") (pin "1") (pintype "passive"))
      (node (ref "R40") (pin "2") (pintype "passive"))
    )
    (net (code "30") (name "Net-(K3B-COM)") (class "Default")
      (node (ref "K3") (pin "6") (pinfunction "COM_6") (pintype "passive"))
      (node (ref "R47") (pin "1") (pintype "passive"))
      (node (ref "R48") (pin "1") (pintype "passive"))
      (node (ref "R52") (pin "1") (pintype "passive"))
      (node (ref "R53") (pin "1") (pintype "passive"))
    )
    (net (code "31") (name "Net-(K4B-COM)") (class "Default")
      (node (ref "K4") (pin "6") (pinfunction "COM_6") (pintype "passive"))
      (node (ref "R48") (pin "2") (pintype "passive"))
      (node (ref "R49") (pin "2") (pintype "passive"))
      (node (ref "R53") (pin "2") (pintype "passive"))
      (node (ref "R54") (pin "2") (pintype "passive"))
    )
    (net (code "32") (name "Net-(K5B-COM)") (class "Default")
      (node (ref "K5") (pin "6") (pinfunction "COM_6") (pintype "passive"))
      (node (ref "R51") (pin "1") (pintype "passive"))
    )
    (net (code "33") (name "Net-(Q2-B)") (class "Default")
      (node (ref "C234") (pin "2") (pintype "passive"))
      (node (ref "Q2") (pin "1") (pinfunction "B_1") (pintype "passive"))
      (node (ref "Q5") (pin "1") (pinfunction "B_1") (pintype "passive"))
      (node (ref "R41") (pin "1") (pintype "passive"))
      (node (ref "U203") (pin "1") (pinfunction "O_1") (pintype "passive"))
    )
    (net (code "34") (name "Net-(Q3-B)") (class "Default")
      (node (ref "Q3") (pin "1") (pinfunction "B_1") (pintype "passive"))
      (node (ref "R37") (pin "2") (pintype "passive"))
      (node (ref "R42") (pin "2") (pintype "passive"))
    )
    (net (code "35") (name "Net-(Q4-B)") (class "Default")
      (node (ref "Q4") (pin "1") (pinfunction "B_1") (pintype "passive"))
      (node (ref "R42") (pin "1") (pintype "passive"))
      (node (ref "R43") (pin "1") (pintype "passive"))
    )
    (net (code "36") (name "Net-(Q6-B)") (class "Default")
      (node (ref "Q6") (pin "1") (pinfunction "B_1") (pintype "passive"))
      (node (ref "R77") (pin "2") (pintype "passive"))
    )
    (net (code "37") (name "Net-(Q7-B)") (class "Default")
      (node (ref "Q7") (pin "1") (pinfunction "B_1") (pintype "passive"))
      (node (ref "R72") (pin "2") (pintype "passive"))
    )
    (net (code "38") (name "Net-(Q8-B)") (class "Default")
      (node (ref "Q8") (pin "1") (pinfunction "B_1") (pintype "passive"))
      (node (ref "R69") (pin "2") (pintype "passive"))
    )
    (net (code "39") (name "Net-(Q201-B)") (class "Default")
      (node (ref "Q201") (pin "1") (pinfunction "B_1") (pintype "passive"))
      (node (ref "U203") (pin "7") (pinfunction "O_7") (pintype "passive"))
    )
    (net (code "40") (name "Net-(Q201-C)") (class "Default")
      (node (ref "C234") (pin "1") (pintype "passive"))
      (node (ref "D23") (pin "3") (pinfunction "A_3") (pintype "passive"))
      (node (ref "Q201") (pin "3") (pinfunction "C_3") (pintype "passive"))
      (node (ref "R36") (pin "2") (pintype "passive"))
      (node (ref "U10") (pin "8") (pinfunction "IOUT_8") (pintype "passive"))
      (node (ref "U203") (pin "2") (pinfunction "-_2") (pintype "passive"))
    )
    (net (code "41") (name "Net-(Q201-E)") (class "Default")
      (node (ref "Q201") (pin "2") (pinfunction "E_2") (pintype "passive"))
      (node (ref "R35") (pin "3") (pinfunction "3_3") (pintype "passive"))
    )
    (net (code "42") (name "Net-(R34-Pad2)") (class "Default")
      (node (ref "R34") (pin "2") (pintype "passive"))
      (node (ref "R35") (pin "1") (pinfunction "1_1") (pintype "passive"))
    )
    (net (code "43") (name "Net-(R55-Pad2)") (class "Default")
      (node (ref "R55") (pin "2") (pintype "passive"))
      (node (ref "R62") (pin "3") (pinfunction "3_3") (pintype "passive"))
    )
    (net (code "44") (name "Net-(R62-Pad1)") (class "Default")
      (node (ref "R62") (pin "1") (pinfunction "1_1") (pintype "passive"))
      (node (ref "R65") (pin "2") (pintype "passive"))
    )
    (net (code "45") (name "Net-(R74-Pad2)") (class "Default")
      (node (ref "R74") (pin "2") (pintype "passive"))
      (node (ref "U8") (pin "15") (pinfunction "15_15") (pintype "passive"))
    )
    (net (code "46") (name "Net-(R75-Pad2)") (class "Default")
      (node (ref "R75") (pin "2") (pintype "passive"))
      (node (ref "U8") (pin "2") (pinfunction "2_2") (pintype "passive"))
    )
    (net (code "47") (name "Net-(U10-COMP)") (class "Default")
      (node (ref "C21") (pin "1") (pintype "passive"))
      (node (ref "U10") (pin "4") (pinfunction "COMP_4") (pintype "passive"))
    )
    (net (code "48") (name "Net-(U10-VR+)") (class "Default")
      (node (ref "R38") (pin "2") (pintype "passive"))
      (node (ref "U10") (pin "2") (pinfunction "VR+_2") (pintype "passive"))
    )
    (net (code "49") (name "Net-(U10-VR-)") (class "Default")
      (node (ref "R45") (pin "1") (pintype "passive"))
      (node (ref "U10") (pin "3") (pinfunction "VR-_3") (pintype "passive"))
    )
    (net (code "50") (name "Net-(U10-~{IOUT})") (class "Default")
      (node (ref "R46") (pin "1") (pintype "passive"))
      (node (ref "U10") (pin "6") (pinfunction "~{IOUT}_6") (pintype "passive"))
    )
    (net (code "51") (name "Net-(U203A-+)") (class "Default")
      (node (ref "D28") (pin "3") (pinfunction "A_3") (pintype "passive"))
      (node (ref "R51") (pin "2") (pintype "passive"))
      (node (ref "U203") (pin "3") (pinfunction "+_3") (pintype "passive"))
    )
    (net (code "52") (name "Net-(U203B-+)") (class "Default")
      (node (ref "R39") (pin "2") (pintype "passive"))
      (node (ref "U203") (pin "5") (pinfunction "+_5") (pintype "passive"))
      (node (ref "U9") (pin "3") (pinfunction "3_3") (pintype "passive"))
    )
    (net (code "53") (name "Net-(U203B--)") (class "Default")
      (node (ref "R35") (pin "2") (pinfunction "2_2") (pintype "passive"))
      (node (ref "U203") (pin "6") (pinfunction "-_6") (pintype "passive"))
    )
    (net (code "54") (name "Net-(U206B-X2)") (class "Default")
      (node (ref "R59") (pin "2") (pintype "passive"))
      (node (ref "U206") (pin "15") (pinfunction "X2_15") (pintype "passive"))
    )
    (net (code "55") (name "Net-(U206B-Y0)") (class "Default")
      (node (ref "R60") (pin "2") (pintype "passive"))
      (node (ref "U206") (pin "1") (pinfunction "Y0_1") (pintype "passive"))
      (node (ref "U208") (pin "7") (pinfunction "O_7") (pintype "passive"))
    )
    (net (code "56") (name "Net-(U206B-Y2)") (class "Default")
      (node (ref "R58") (pin "2") (pintype "passive"))
      (node (ref "R61") (pin "1") (pintype "passive"))
      (node (ref "U206") (pin "2") (pinfunction "Y2_2") (pintype "passive"))
      (node (ref "U208") (pin "1") (pinfunction "O_1") (pintype "passive"))
    )
    (net (code "57") (name "Net-(U206C-Y)") (class "Default")
      (node (ref "R71") (pin "2") (pintype "passive"))
      (node (ref "R75") (pin "1") (pintype "passive"))
      (node (ref "U206") (pin "3") (pinfunction "Y_3") (pintype "passive"))
    )
    (net (code "58") (name "Net-(U206C-Y1)") (class "Default")
      (node (ref "R70") (pin "2") (pintype "passive"))
      (node (ref "R74") (pin "1") (pintype "passive"))
      (node (ref "U206") (pin "5") (pinfunction "Y1_5") (pintype "passive"))
    )
    (net (code "59") (name "Net-(U206C-Y3)") (class "Default")
      (node (ref "R73") (pin "2") (pintype "passive"))
      (node (ref "U206") (pin "4") (pinfunction "Y3_4") (pintype "passive"))
    )
    (net (code "60") (name "Net-(U208A--)") (class "Default")
      (node (ref "R58") (pin "1") (pintype "passive"))
      (node (ref "R62") (pin "2") (pinfunction "2_2") (pintype "passive"))
      (node (ref "R64") (pin "1") (pintype "passive"))
      (node (ref "U208") (pin "2") (pinfunction "-_2") (pintype "passive"))
    )
    (net (code "61") (name "Net-(U208B--)") (class "Default")
      (node (ref "R60") (pin "1") (pintype "passive"))
      (node (ref "R61") (pin "2") (pintype "passive"))
      (node (ref "R63") (pin "1") (pintype "passive"))
      (node (ref "U208") (pin "6") (pinfunction "-_6") (pintype "passive"))
    )
    (net (code "62") (name "Net-(U209A-+)") (class "Default")
      (node (ref "D30") (pin "3") (pinfunction "A_3") (pintype "passive"))
      (node (ref "R66") (pin "2") (pintype "passive"))
      (node (ref "U209") (pin "3") (pinfunction "+_3") (pintype "passive"))
    )
    (net (code "63") (name "Net-(U209A--)") (class "Default")
      (node (ref "R68") (pin "1") (pintype "passive"))
      (node (ref "R71") (pin "1") (pintype "passive"))
      (node (ref "U209") (pin "1") (pinfunction "O_1") (pintype "passive"))
      (node (ref "U209") (pin "2") (pinfunction "-_2") (pintype "passive"))
    )
    (net (code "64") (name "Net-(U209B--)") (class "Default")
      (node (ref "R67") (pin "1") (pintype "passive"))
      (node (ref "R68") (pin "2") (pintype "passive"))
      (node (ref "U209") (pin "6") (pinfunction "-_6") (pintype "passive"))
    )
    (net (code "65") (name "Net-(U209B-O)") (class "Default")
      (node (ref "R65") (pin "1") (pintype "passive"))
      (node (ref "R67") (pin "2") (pintype "passive"))
      (node (ref "R70") (pin "1") (pintype "passive"))
      (node (ref "U209") (pin "7") (pinfunction "O_7") (pintype "passive"))
    )
    (net (code "66") (name "P5VA") (class "Default")
      (node (ref "C10") (pin "1") (pintype "passive"))
      (node (ref "C11") (pin "1") (pintype "passive"))
      (node (ref "C24") (pin "1") (pintype "passive"))
      (node (ref "R37") (pin "1") (pintype "passive"))
      (node (ref "U206") (pin "16") (pinfunction "VCC_16") (pintype "passive"))
      (node (ref "U208") (pin "4") (pinfunction "VEE_4") (pintype "passive"))
      (node (ref "U8") (pin "12") (pinfunction "VL_12") (pintype "power_in"))
    )
    (net (code "67") (name "P5VREL") (class "Default")
      (node (ref "D31") (pin "3") (pinfunction "K_3") (pintype "passive"))
      (node (ref "D32") (pin "3") (pinfunction "K_3") (pintype "passive"))
      (node (ref "D33") (pin "3") (pinfunction "K_3") (pintype "passive"))
      (node (ref "K3") (pin "1") (pinfunction "1_1") (pintype "passive"))
      (node (ref "K4") (pin "1") (pinfunction "1_1") (pintype "passive"))
      (node (ref "K5") (pin "1") (pinfunction "1_1") (pintype "passive"))
    )
    (net (code "68") (name "P15VA") (class "Default")
      (node (ref "C12") (pin "1") (pintype "passive"))
      (node (ref "C13") (pin "1") (pintype "passive"))
      (node (ref "C14") (pin "1") (pintype "passive"))
      (node (ref "C20") (pin "2") (pintype "passive"))
      (node (ref "D23") (pin "2") (pinfunction "A_2") (pintype "passive"))
      (node (ref "D28") (pin "2") (pinfunction "A_2") (pintype "passive"))
      (node (ref "D30") (pin "2") (pinfunction "A_2") (pintype "passive"))
      (node (ref "Q2") (pin "3") (pinfunction "C_3") (pintype "passive"))
      (node (ref "R207") (pin "1") (pintype "passive"))
      (node (ref "R34") (pin "1") (pintype "passive"))
      (node (ref "U10") (pin "1") (pinfunction "VCC_1") (pintype "passive"))
      (node (ref "U203") (pin "8") (pinfunction "VCC_8") (pintype "passive"))
      (node (ref "U209") (pin "4") (pinfunction "VEE_4") (pintype "passive"))
      (node (ref "U8") (pin "13") (pinfunction "VCC_13") (pintype "power_in"))
      (node (ref "U9") (pin "1") (pinfunction "1_1") (pintype "passive"))
      (node (ref "U9") (pin "2") (pinfunction "2_2") (pintype "passive"))
    )
    (net (code "69") (name "VREF") (class "Default") (node (ref "R38") (pin "1") (pintype "passive")))
    (net (code "70") (name "unconnected-(D29-A-Pad2)") (class "Default")
      (node (ref "D29") (pin "2") (pinfunction "A_2") (pintype "passive"))
    )
    (net (code "71") (name "unconnected-(K3B-NC-Pad7)") (class "Default")
      (node (ref "K3") (pin "7") (pinfunction "NC_7") (pintype "passive"))
    )
    (net (code "72") (name "unconnected-(K4B-NC-Pad7)") (class "Default")
      (node (ref "K4") (pin "7") (pinfunction "NC_7") (pintype "passive"))
    )
  )
)
